# Sensors.net
KiCad netlist of a schematic drawn in Altium Designer
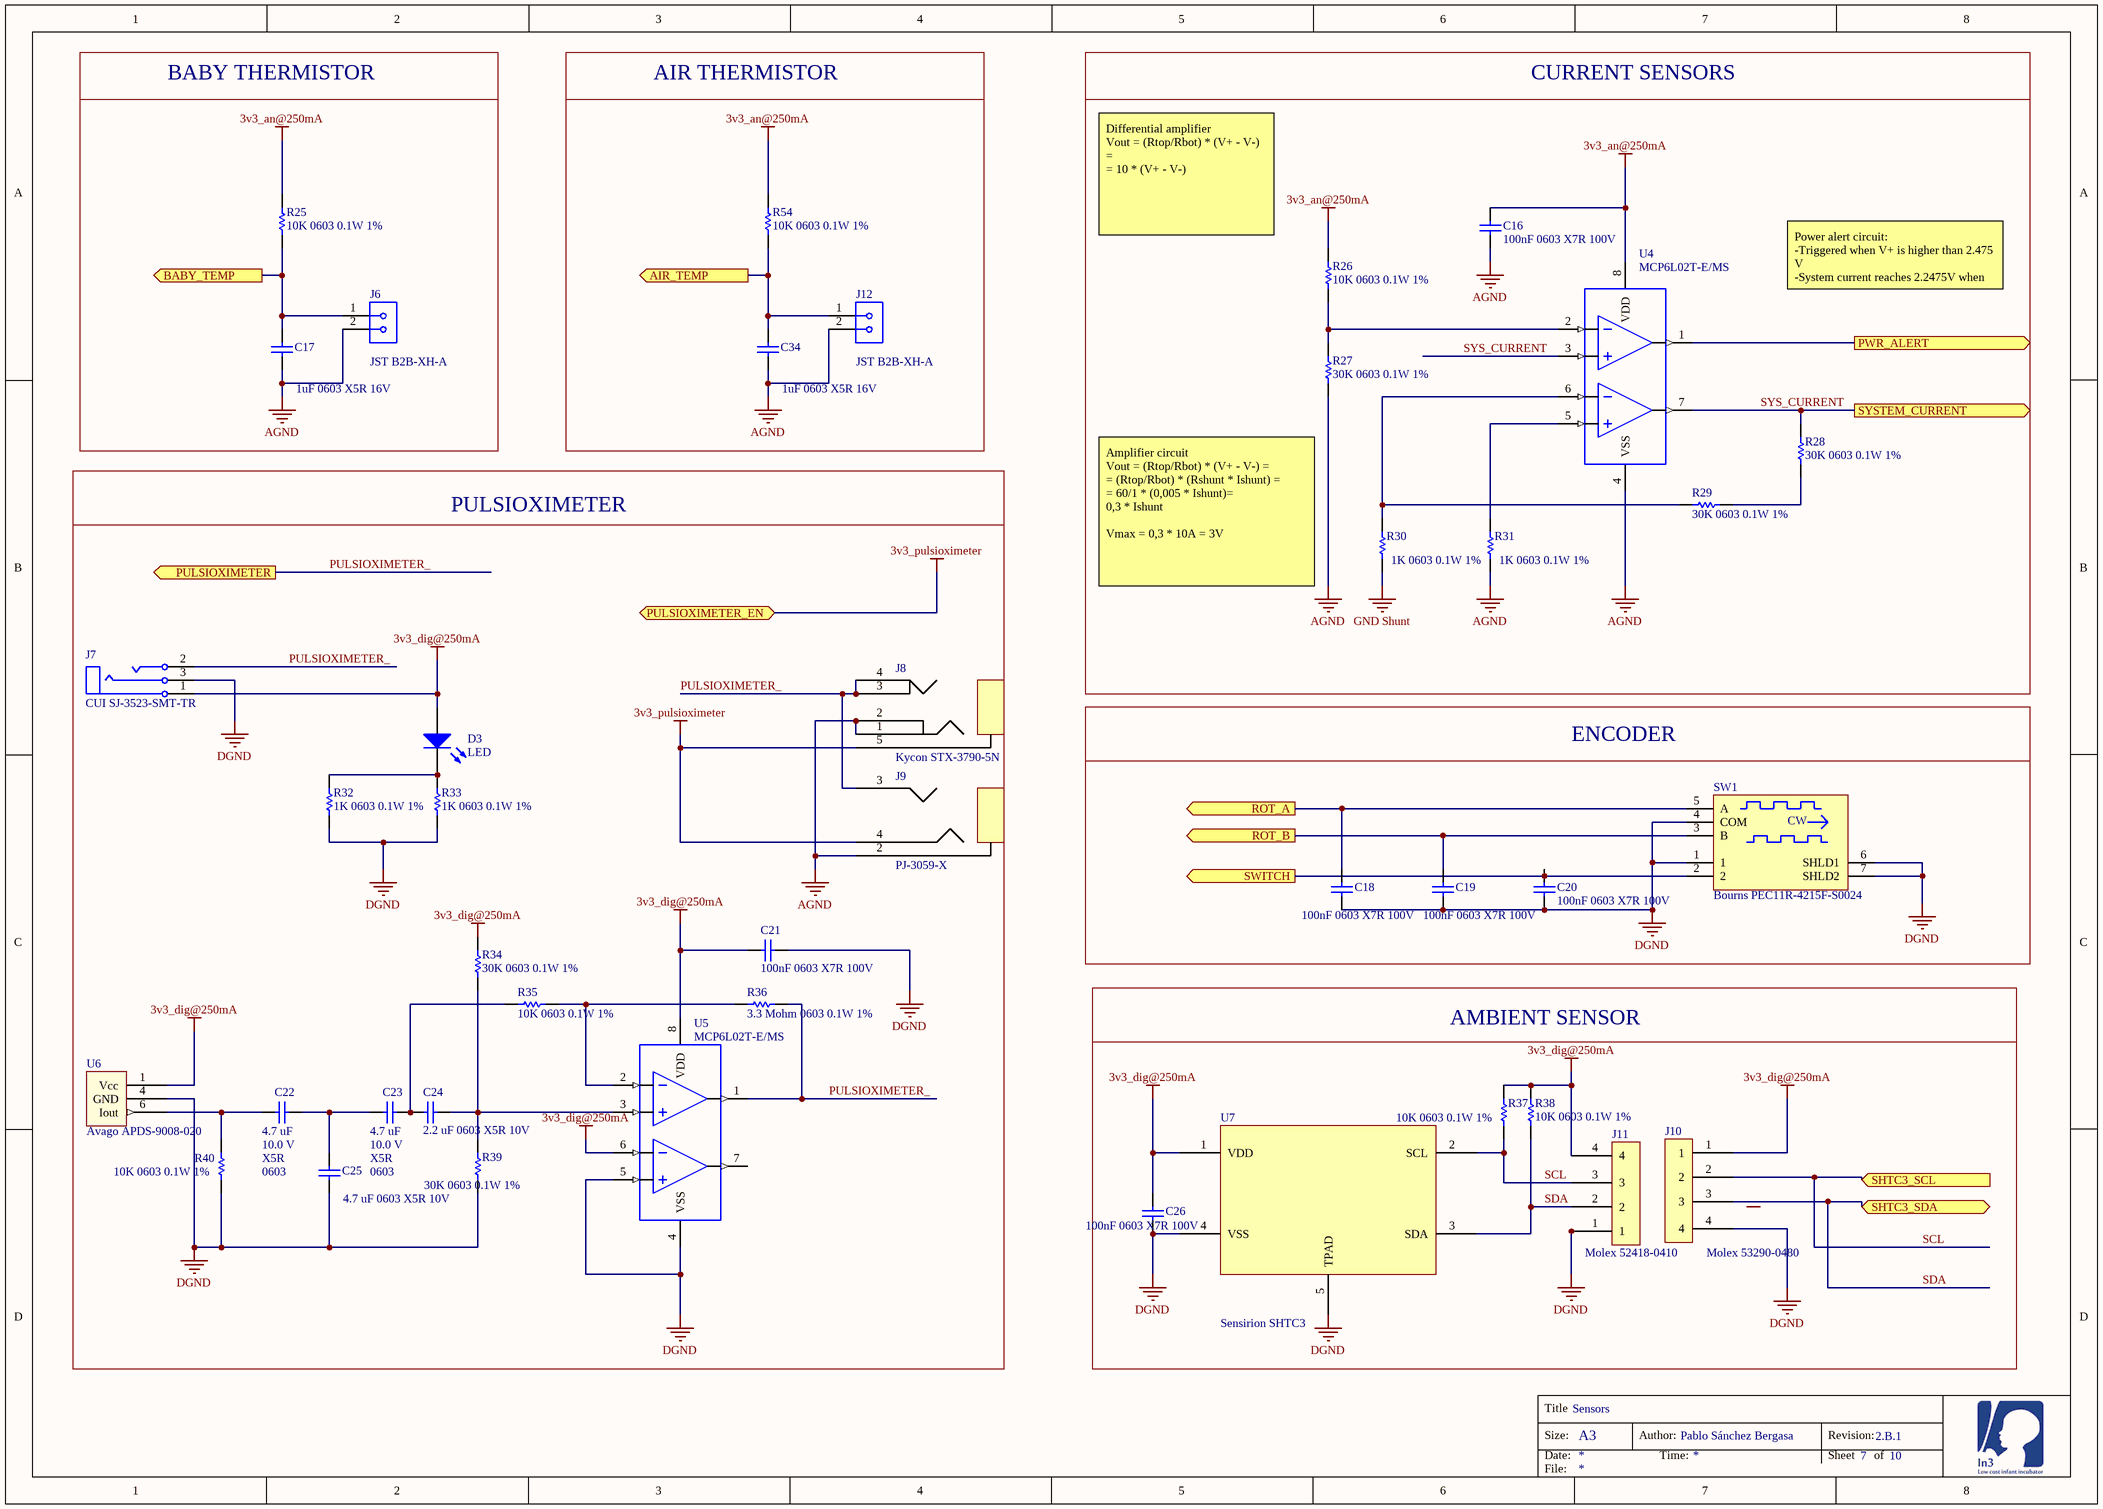
[diagram p0: Sensors.SchDoc]

(export (version "E")
  (design (tool "Eeschema 10.0.6"))
  (components
    (comp (ref "C16")
      (value "100nF 0603 X7R 100V")
      (footprint "CAPC1608X60X35NL10T15")
      (fields (field (name "MANUFACTURAR PART NUMBER") "CC0603KRX7R0BB104"))
      (libsource (lib "CommunityVault") (part "CMP-c41a0d2b65641bdd-3"))
    )
    (comp (ref "C17")
      (value "1uF 0603 X5R 16V")
      (footprint "CAPC1608X60X35NL10T15")
      (fields (field (name "MANUFACTURER PART NUMBER") "GRM185R61C105KE44D"))
      (libsource (lib "CommunityVault") (part "CMP-119984-2"))
    )
    (comp (ref "C18")
      (value "100nF 0603 X7R 100V")
      (footprint "CAPC1608X60X35NL10T15")
      (fields (field (name "MANUFACTURAR PART NUMBER") "CC0603KRX7R0BB104"))
      (libsource (lib "CommunityVault") (part "CMP-c41a0d2b65641bdd-3"))
    )
    (comp (ref "C19")
      (value "100nF 0603 X7R 100V")
      (footprint "CAPC1608X60X35NL10T15")
      (fields (field (name "MANUFACTURAR PART NUMBER") "CC0603KRX7R0BB104"))
      (libsource (lib "CommunityVault") (part "CMP-c41a0d2b65641bdd-3"))
    )
    (comp (ref "C20")
      (value "100nF 0603 X7R 100V")
      (footprint "CAPC1608X60X35NL10T15")
      (fields (field (name "MANUFACTURAR PART NUMBER") "CC0603KRX7R0BB104"))
      (libsource (lib "CommunityVault") (part "CMP-c41a0d2b65641bdd-3"))
    )
    (comp (ref "C21")
      (value "100nF 0603 X7R 100V")
      (footprint "CAPC1608X60X35NL10T15")
      (fields (field (name "MANUFACTURAR PART NUMBER") "CC0603KRX7R0BB104"))
      (libsource (lib "CommunityVault") (part "CMP-c41a0d2b65641bdd-3"))
    )
    (comp (ref "C22")
      (value "4.7 uF 0603 X5R 10V")
      (footprint "PCB-o44e25ijbg7jfnbnmamr-1")
      (description "CL10 Series 4.7 uF 10 V ±10 % Tolerance X5R SMT Multilayer Ceramic Capacitor")
      (fields
        (field (name "CAPACITANCE") "4.7 uF")
        (field (name "MANUFACTURER PART NUMBER") "CL10A475KP8NNNC")
        (field (name "DIELECTRIC CHARACTERISTIC") "X5R")
        (field (name "VOLTAGE RATING (DC)") "10.0 V")
        (field (name "CASE/PACKAGE") "0603")
      )
      (libsource (lib "CommunityVault") (part "CMP-4caf8516eb679368-2"))
    )
    (comp (ref "C23")
      (value "4.7 uF 0603 X5R 10V")
      (footprint "PCB-o44e25ijbg7jfnbnmamr-1")
      (description "CL10 Series 4.7 uF 10 V ±10 % Tolerance X5R SMT Multilayer Ceramic Capacitor")
      (fields
        (field (name "CAPACITANCE") "4.7 uF")
        (field (name "MANUFACTURER PART NUMBER") "CL10A475KP8NNNC")
        (field (name "DIELECTRIC CHARACTERISTIC") "X5R")
        (field (name "VOLTAGE RATING (DC)") "10.0 V")
        (field (name "CASE/PACKAGE") "0603")
      )
      (libsource (lib "CommunityVault") (part "CMP-4caf8516eb679368-2"))
    )
    (comp (ref "C24")
      (value "2.2 uF 0603 X5R 10V")
      (footprint "PCB-ut6qvzar43b06cy077h6-1")
      (description "Capacitor: ceramic; MLCC; 2.2uF; 10V; X5R; ±10%; SMD; 0603; -55÷85°C")
      (fields (field (name "MANUFACTURER PART NUMBER") "CL10A225KP8NNNC"))
      (libsource (lib "CommunityVault") (part "CMP-3568fc1ddfcfeaaf-3"))
    )
    (comp (ref "C25")
      (value "4.7 uF 0603 X5R 10V")
      (footprint "PCB-o44e25ijbg7jfnbnmamr-1")
      (description "CL10 Series 4.7 uF 10 V ±10 % Tolerance X5R SMT Multilayer Ceramic Capacitor")
      (fields (field (name "MANUFACTURER PART NUMBER") "CL10A475KP8NNNC"))
      (libsource (lib "CommunityVault") (part "CMP-4caf8516eb679368-2"))
    )
    (comp (ref "C26")
      (value "100nF 0603 X7R 100V")
      (footprint "CAPC1608X60X35NL10T15")
      (fields (field (name "MANUFACTURAR PART NUMBER") "CC0603KRX7R0BB104"))
      (libsource (lib "CommunityVault") (part "CMP-c41a0d2b65641bdd-3"))
    )
    (comp (ref "C34")
      (value "1uF 0603 X5R 16V")
      (footprint "CAPC1608X60X35NL10T15")
      (fields (field (name "MANUFACTURER PART NUMBER") "GRM185R61C105KE44D"))
      (libsource (lib "CommunityVault") (part "CMP-119984-2"))
    )
    (comp (ref "D3")
      (value "LED")
      (footprint "Diode")
      (description "Green 2.5 x 2 x 2.8 mm 20° Clear 2700 mcd 3.3 V Subminiature Solid State LED SMT")
      (fields (field (name "MANUFACTURER PART NUMBER") "AM2520ZGC09"))
      (libsource (lib "CommunityVault") (part "CMP-528b9bd0c0208d4c-1"))
    )
    (comp (ref "J6")
      (value "JST B2B-XH-A")
      (footprint "PCB-pp1at3pfx7vls1ur72ey-1")
      (description "Conn Shrouded Header HDR 2 POS 2.5mm Solder ST Thru-Hole Box")
      (fields (field (name "MANUFACTURER PART NUMBER") "B2B-XH-A"))
      (libsource (lib "CommunityVault") (part "CMP-1d67d451da9ec2a0-3"))
    )
    (comp (ref "J7")
      (value "CUI SJ-3523-SMT-TR")
      (footprint "PCB-wpf2idtw6ymbd7wafvje-1")
      (description "Conn 3.5MM Stereo Jack F 3 POS Solder RA SMD 3 Terminal 1 Port T/R")
      (fields (field (name "MANUFACTURER PART NUMBER") "SJ-3523-SMT-TR"))
      (libsource (lib "FavoritesLibrary") (part "SYM-9d6655e7545842a1-4"))
    )
    (comp (ref "J8")
      (value "Kycon STX-3790-5N")
      (footprint "PCB-4j7k1xhz8vc7zbr3u2za-1")
      (description "Conn Audio RCP 5 POS Solder ST Thru-Hole 5 Terminal 1 Port")
      (fields (field (name "MANUFACTURER PART NUMBER") "STX-3790-5N"))
      (libsource (lib "FavoritesLibrary") (part "SYM-d3711b49a5340cb6-1"))
    )
    (comp (ref "J9")
      (value "PJ-3059-X")
      (footprint "PCB-ylnrsqqp1zh2nrt13053-1")
      (description "3.5mm Plug-in headphone holder")
      (libsource (lib "CommunityVault") (part "CMP-qu24ppwf8ue4q4dth5co-2"))
    )
    (comp (ref "J10")
      (value "Molex 53290-0480")
      (footprint "PCB-az7j7v00du7ll54n3o04-1")
      (description "Molex; SER Number 53290; 2mm Pitch 4Way 1Row Straight PCB Header; Solder Term; 1.5A")
      (fields (field (name "MANUFACTURER PART NUMBER") "53290-0480"))
      (libsource (lib "FavoritesLibrary") (part "SYM-77b5bebc9fe3a872-1"))
    )
    (comp (ref "J11")
      (value "Molex 52418-0410")
      (footprint "PCB-2exqb8kt510pgx9iz0yo-1")
      (description "2.00mm Pitch Board-to-Board Receptacle, Right Angle, Single Row, Friction Lock, 4 Circuits")
      (fields (field (name "MANUFACTURER PART NUMBER") "52418-0410"))
      (libsource (lib "FavoritesLibrary") (part "SYM-efff26f6ba583038-1"))
    )
    (comp (ref "J12")
      (value "JST B2B-XH-A")
      (footprint "PCB-pp1at3pfx7vls1ur72ey-1")
      (description "Conn Shrouded Header HDR 2 POS 2.5mm Solder ST Thru-Hole Box")
      (fields (field (name "MANUFACTURER PART NUMBER") "B2B-XH-A"))
      (libsource (lib "CommunityVault") (part "CMP-1d67d451da9ec2a0-3"))
    )
    (comp (ref "R25")
      (value "10K 0603 0.1W 1%")
      (footprint "RESC1609X55X30ML10T20")
      (fields (field (name "TOLERANCE") "1%") (field (name "MANUFACTURER PART NUMBER") "ERJ-3GEYJ101V"))
      (libsource (lib "CommunityVault") (part "CMP-4716590-9"))
    )
    (comp (ref "R26")
      (value "10K 0603 0.1W 1%")
      (footprint "RESC1609X55X30ML10T20")
      (fields (field (name "TOLERANCE") "1%") (field (name "MANUFACTURER PART NUMBER") "ERJ-3GEYJ101V"))
      (libsource (lib "CommunityVault") (part "CMP-4716590-9"))
    )
    (comp (ref "R27")
      (value "30K 0603 0.1W 1%")
      (footprint "RESC1609X55X30ML10T20")
      (fields (field (name "TOLERANCE") "1%"))
      (libsource (lib "CommunityVault") (part "CMP-3655986-6"))
    )
    (comp (ref "R28")
      (value "30K 0603 0.1W 1%")
      (footprint "RESC1609X55X30ML10T20")
      (fields (field (name "TOLERANCE") "1%"))
      (libsource (lib "CommunityVault") (part "CMP-3655986-6"))
    )
    (comp (ref "R29")
      (value "30K 0603 0.1W 1%")
      (footprint "RESC1609X55X30ML10T20")
      (fields (field (name "TOLERANCE") "1%"))
      (libsource (lib "CommunityVault") (part "CMP-3655986-6"))
    )
    (comp (ref "R30")
      (value "1K 0603 0.1W 1%")
      (footprint "RESC1609X55X30ML10T20")
      (fields (field (name "MANUFACTURER PART NUMBER") "CR0603-FX-1001ELF"))
      (libsource (lib "CommunityVault") (part "CMP-a61f6f36030f79d8-4"))
    )
    (comp (ref "R31")
      (value "1K 0603 0.1W 1%")
      (footprint "RESC1609X55X30ML10T20")
      (fields (field (name "MANUFACTURER PART NUMBER") "CR0603-FX-1001ELF"))
      (libsource (lib "CommunityVault") (part "CMP-a61f6f36030f79d8-4"))
    )
    (comp (ref "R32")
      (value "1K 0603 0.1W 1%")
      (footprint "RESC1609X55X30ML10T20")
      (fields (field (name "MANUFACTURER PART NUMBER") "CR0603-FX-1001ELF"))
      (libsource (lib "CommunityVault") (part "CMP-a61f6f36030f79d8-4"))
    )
    (comp (ref "R33")
      (value "1K 0603 0.1W 1%")
      (footprint "RESC1609X55X30ML10T20")
      (fields (field (name "MANUFACTURER PART NUMBER") "CR0603-FX-1001ELF"))
      (libsource (lib "CommunityVault") (part "CMP-a61f6f36030f79d8-4"))
    )
    (comp (ref "R34")
      (value "30K 0603 0.1W 1%")
      (footprint "RESC1609X55X30ML10T20")
      (fields (field (name "TOLERANCE") "1%"))
      (libsource (lib "CommunityVault") (part "CMP-3655986-6"))
    )
    (comp (ref "R35")
      (value "10K 0603 0.1W 1%")
      (footprint "RESC1609X55X30ML10T20")
      (fields (field (name "TOLERANCE") "1%") (field (name "MANUFACTURER PART NUMBER") "ERJ-3GEYJ101V"))
      (libsource (lib "CommunityVault") (part "CMP-4716590-9"))
    )
    (comp (ref "R36")
      (value "3.3 Mohm 0603 0.1W 1%")
      (footprint "PCB-mzxdg9kz9211q53vmmjz-1")
      (description "Res Thick Film 1.6 x 0.8 mm 330K Ohm 1% 0.1W(1/10W) 100ppm/ C Molded SMD Paper T/R")
      (fields (field (name "MANUFACTURER PART NUMBER") "RC0603FR-07330KL"))
      (libsource (lib "CommunityVault") (part "CMP-0de3c699ccb2d224-2"))
    )
    (comp (ref "R37")
      (value "10K 0603 0.1W 1%")
      (footprint "RESC1609X55X30ML10T20")
      (fields (field (name "TOLERANCE") "1%") (field (name "MANUFACTURER PART NUMBER") "ERJ-3GEYJ101V"))
      (libsource (lib "CommunityVault") (part "CMP-4716590-9"))
    )
    (comp (ref "R38")
      (value "10K 0603 0.1W 1%")
      (footprint "RESC1609X55X30ML10T20")
      (fields (field (name "TOLERANCE") "1%") (field (name "MANUFACTURER PART NUMBER") "ERJ-3GEYJ101V"))
      (libsource (lib "CommunityVault") (part "CMP-4716590-9"))
    )
    (comp (ref "R39")
      (value "30K 0603 0.1W 1%")
      (footprint "RESC1609X55X30ML10T20")
      (fields (field (name "TOLERANCE") "1%"))
      (libsource (lib "CommunityVault") (part "CMP-3655986-6"))
    )
    (comp (ref "R40")
      (value "10K 0603 0.1W 1%")
      (footprint "RESC1609X55X30ML10T20")
      (fields (field (name "TOLERANCE") "1%") (field (name "MANUFACTURER PART NUMBER") "ERJ-3GEYJ101V"))
      (libsource (lib "CommunityVault") (part "CMP-4716590-9"))
    )
    (comp (ref "R54")
      (value "10K 0603 0.1W 1%")
      (footprint "RESC1609X55X30ML10T20")
      (fields (field (name "TOLERANCE") "1%") (field (name "MANUFACTURER PART NUMBER") "ERJ-3GEYJ101V"))
      (libsource (lib "CommunityVault") (part "CMP-4716590-9"))
    )
    (comp (ref "SW1")
      (value "Bourns PEC11R-4215F-S0024")
      (footprint "BOUR-PEC11R-4XXXF-SXXXX_V")
      (description "12 mm Incremental Encoder, 24 Detent, -30 to 70 degC, 5-Pin THD, RoHS, Bulk")
      (fields (field (name "MANUFACTURER PART NUMBER") "PEC11R-4215F-S0024"))
      (libsource (lib "FavoritesLibrary") (part "SW-ENCODER-5"))
    )
    (comp (ref "U4")
      (value "MCP6L02T-E/MS")
      (footprint "PCB-e8n0jpjj0ctkgxf737qv-1")
      (description "Microchip MCP6L02T-E/MS, Dual Op Amp, 1MHz Rail-Rail, 1.8 to 6 V, 8-Pin MSOP")
      (libsource (lib "CommunityVault") (part "CMP-1319549-4"))
    )
    (comp (ref "U5")
      (value "MCP6L02T-E/MS")
      (footprint "PCB-e8n0jpjj0ctkgxf737qv-1")
      (description "Microchip MCP6L02T-E/MS, Dual Op Amp, 1MHz Rail-Rail, 1.8 to 6 V, 8-Pin MSOP")
      (libsource (lib "CommunityVault") (part "CMP-1319549-4"))
    )
    (comp (ref "U6")
      (value "Avago APDS-9008-020")
      (footprint "PCB-5zuy5omviewwv0vuvsb9-1")
      (description "Ambient Light Sensor Photodetector 6-Pin SMD T/R")
      (fields (field (name "MANUFACTURER PART NUMBER") "APDS-9008-020"))
      (libsource (lib "CommunityVault") (part "SYM-1600df74f371c9c7-1"))
    )
    (comp (ref "U7")
      (value "Sensirion SHTC3")
      (footprint "DFN4 2x2 + EP")
      (description "Humidity & Temperature Sensor ±2% RH ±0, 2°C I2C DFN4")
      (libsource (lib "CommunityVault") (part "SHTC3"))
    )
  )
  (nets
    (net (code "1") (name "/AIR_TEMP") (class "Default")
      (node (ref "C34") (pin "1") (pinfunction "1_1") (pintype "passive"))
      (node (ref "J12") (pin "1") (pinfunction "1_1") (pintype "passive"))
      (node (ref "R54") (pin "2") (pinfunction "2_2") (pintype "passive"))
    )
    (net (code "2") (name "/BABY_TEMP") (class "Default")
      (node (ref "C17") (pin "1") (pinfunction "1_1") (pintype "passive"))
      (node (ref "J6") (pin "1") (pinfunction "1_1") (pintype "passive"))
      (node (ref "R25") (pin "2") (pinfunction "2_2") (pintype "passive"))
    )
    (net (code "3") (name "/PULSIOXIMETER_") (class "Default")
      (node (ref "J7") (pin "2") (pinfunction "TIP_2") (pintype "passive"))
      (node (ref "J8") (pin "3") (pinfunction "RIGHT_3") (pintype "passive"))
      (node (ref "J8") (pin "4") (pinfunction "LEFT_4") (pintype "passive"))
      (node (ref "J9") (pin "3") (pinfunction "LEFT_3") (pintype "passive"))
      (node (ref "R36") (pin "2") (pinfunction "2_2") (pintype "passive"))
      (node (ref "U5") (pin "1") (pinfunction "VOUTA_1") (pintype "output"))
    )
    (net (code "4") (name "/PWR_ALERT") (class "Default")
      (node (ref "U4") (pin "1") (pinfunction "VOUTA_1") (pintype "output"))
    )
    (net (code "5") (name "/ROT_A") (class "Default")
      (node (ref "C18") (pin "2") (pinfunction "2_2") (pintype "passive"))
      (node (ref "SW1") (pin "5") (pinfunction "A_5") (pintype "passive"))
    )
    (net (code "6") (name "/ROT_B") (class "Default")
      (node (ref "C19") (pin "2") (pinfunction "2_2") (pintype "passive"))
      (node (ref "SW1") (pin "3") (pinfunction "B_3") (pintype "passive"))
    )
    (net (code "7") (name "/SCL") (class "Default")
      (node (ref "J10") (pin "2") (pinfunction "2_2") (pintype "passive"))
      (node (ref "J11") (pin "3") (pinfunction "3_3") (pintype "passive"))
      (node (ref "R37") (pin "2") (pinfunction "2_2") (pintype "passive"))
      (node (ref "U7") (pin "2") (pinfunction "SCL_2") (pintype "passive"))
    )
    (net (code "8") (name "/SDA") (class "Default")
      (node (ref "J10") (pin "3") (pinfunction "3_3") (pintype "passive"))
      (node (ref "J11") (pin "2") (pinfunction "2_2") (pintype "passive"))
      (node (ref "R38") (pin "2") (pinfunction "2_2") (pintype "passive"))
      (node (ref "U7") (pin "3") (pinfunction "SDA_3") (pintype "passive"))
    )
    (net (code "9") (name "/SWITCH") (class "Default")
      (node (ref "C20") (pin "2") (pinfunction "2_2") (pintype "passive"))
      (node (ref "SW1") (pin "2") (pinfunction "2_2") (pintype "passive"))
    )
    (net (code "10") (name "/SYS_CURRENT") (class "Default")
      (node (ref "R28") (pin "1") (pinfunction "1_1") (pintype "passive"))
      (node (ref "U4") (pin "3") (pinfunction "VINA+_3") (pintype "input"))
      (node (ref "U4") (pin "7") (pinfunction "OUT_B_7") (pintype "output"))
    )
    (net (code "11") (name "3v3_an@250mA") (class "Default")
      (node (ref "C16") (pin "2") (pinfunction "2_2") (pintype "passive"))
      (node (ref "R25") (pin "1") (pinfunction "1_1") (pintype "passive"))
      (node (ref "R26") (pin "1") (pinfunction "1_1") (pintype "passive"))
      (node (ref "R54") (pin "1") (pinfunction "1_1") (pintype "passive"))
      (node (ref "U4") (pin "8") (pinfunction "VDD_8") (pintype "power_in"))
    )
    (net (code "12") (name "3v3_dig@250mA") (class "Default")
      (node (ref "C21") (pin "2") (pinfunction "2_2") (pintype "passive"))
      (node (ref "C26") (pin "2") (pinfunction "2_2") (pintype "passive"))
      (node (ref "D3") (pin "1") (pinfunction "A_1") (pintype "passive"))
      (node (ref "J10") (pin "1") (pinfunction "1_1") (pintype "passive"))
      (node (ref "J11") (pin "4") (pinfunction "4_4") (pintype "passive"))
      (node (ref "J7") (pin "1") (pinfunction "SLEEVE_1") (pintype "passive"))
      (node (ref "R34") (pin "1") (pinfunction "1_1") (pintype "passive"))
      (node (ref "R37") (pin "1") (pinfunction "1_1") (pintype "passive"))
      (node (ref "R38") (pin "1") (pinfunction "1_1") (pintype "passive"))
      (node (ref "U5") (pin "6") (pinfunction "VINB-_6") (pintype "input"))
      (node (ref "U5") (pin "8") (pinfunction "VDD_8") (pintype "power_in"))
      (node (ref "U6") (pin "1") (pinfunction "Vcc_1") (pintype "power_in"))
      (node (ref "U7") (pin "1") (pinfunction "VDD_1") (pintype "passive"))
    )
    (net (code "13") (name "3v3_pulsioximeter") (class "Default")
      (node (ref "J8") (pin "5") (pinfunction "GND_5") (pintype "passive"))
      (node (ref "J9") (pin "4") (pinfunction "RIGHT_4") (pintype "passive"))
    )
    (net (code "14") (name "AGND") (class "Default")
      (node (ref "C16") (pin "1") (pinfunction "1_1") (pintype "passive"))
      (node (ref "C17") (pin "2") (pinfunction "2_2") (pintype "passive"))
      (node (ref "C34") (pin "2") (pinfunction "2_2") (pintype "passive"))
      (node (ref "J12") (pin "2") (pinfunction "2_2") (pintype "passive"))
      (node (ref "J6") (pin "2") (pinfunction "2_2") (pintype "passive"))
      (node (ref "J8") (pin "1") (pinfunction "RIGHT_1") (pintype "passive"))
      (node (ref "J8") (pin "2") (pinfunction "RIGHT_2") (pintype "passive"))
      (node (ref "J9") (pin "2") (pinfunction "GND_2") (pintype "passive"))
      (node (ref "R27") (pin "2") (pinfunction "2_2") (pintype "passive"))
      (node (ref "R31") (pin "1") (pinfunction "1_1") (pintype "passive"))
      (node (ref "U4") (pin "4") (pinfunction "VSS_4") (pintype "power_in"))
    )
    (net (code "15") (name "DGND") (class "Default")
      (node (ref "C18") (pin "1") (pinfunction "1_1") (pintype "passive"))
      (node (ref "C19") (pin "1") (pinfunction "1_1") (pintype "passive"))
      (node (ref "C20") (pin "1") (pinfunction "1_1") (pintype "passive"))
      (node (ref "C21") (pin "1") (pinfunction "1_1") (pintype "passive"))
      (node (ref "C25") (pin "2") (pinfunction "2_2") (pintype "passive"))
      (node (ref "C26") (pin "1") (pinfunction "1_1") (pintype "passive"))
      (node (ref "J10") (pin "4") (pinfunction "4_4") (pintype "passive"))
      (node (ref "J11") (pin "1") (pinfunction "1_1") (pintype "passive"))
      (node (ref "J7") (pin "3") (pinfunction "RING_3") (pintype "passive"))
      (node (ref "R32") (pin "1") (pinfunction "1_1") (pintype "passive"))
      (node (ref "R33") (pin "1") (pinfunction "1_1") (pintype "passive"))
      (node (ref "R39") (pin "2") (pinfunction "2_2") (pintype "passive"))
      (node (ref "R40") (pin "1") (pinfunction "1_1") (pintype "passive"))
      (node (ref "SW1") (pin "1") (pinfunction "1_1") (pintype "passive"))
      (node (ref "SW1") (pin "4") (pinfunction "COM_4") (pintype "passive"))
      (node (ref "SW1") (pin "6") (pinfunction "SHLD1_6") (pintype "passive"))
      (node (ref "SW1") (pin "7") (pinfunction "SHLD2_7") (pintype "passive"))
      (node (ref "U5") (pin "4") (pinfunction "VSS_4") (pintype "power_in"))
      (node (ref "U5") (pin "5") (pinfunction "VINB+_5") (pintype "input"))
      (node (ref "U6") (pin "4") (pinfunction "GND_4") (pintype "power_in"))
      (node (ref "U7") (pin "4") (pinfunction "VSS_4") (pintype "passive"))
      (node (ref "U7") (pin "5") (pinfunction "TPAD_5") (pintype "passive"))
    )
    (net (code "16") (name "GND Shunt") (class "Default")
      (node (ref "R30") (pin "1") (pinfunction "1_1") (pintype "passive"))
    )
    (net (code "17") (name "Net-(C22-Pad1)") (class "Default")
      (node (ref "C22") (pin "1") (pinfunction "1_1") (pintype "passive"))
      (node (ref "C23") (pin "2") (pinfunction "2_2") (pintype "passive"))
      (node (ref "C25") (pin "1") (pinfunction "1_1") (pintype "passive"))
    )
    (net (code "18") (name "Net-(C23-Pad1)") (class "Default")
      (node (ref "C23") (pin "1") (pinfunction "1_1") (pintype "passive"))
      (node (ref "C24") (pin "2") (pinfunction "2_2") (pintype "passive"))
      (node (ref "R35") (pin "1") (pinfunction "1_1") (pintype "passive"))
    )
    (net (code "19") (name "Net-(D3-K)") (class "Default")
      (node (ref "D3") (pin "2") (pinfunction "K_2") (pintype "passive"))
      (node (ref "R32") (pin "2") (pinfunction "2_2") (pintype "passive"))
      (node (ref "R33") (pin "2") (pinfunction "2_2") (pintype "passive"))
    )
    (net (code "20") (name "Net-(R28-Pad2)") (class "Default")
      (node (ref "R28") (pin "2") (pinfunction "2_2") (pintype "passive"))
      (node (ref "R29") (pin "2") (pinfunction "2_2") (pintype "passive"))
    )
    (net (code "21") (name "Net-(U4-VINA-)") (class "Default")
      (node (ref "R26") (pin "2") (pinfunction "2_2") (pintype "passive"))
      (node (ref "R27") (pin "1") (pinfunction "1_1") (pintype "passive"))
      (node (ref "U4") (pin "2") (pinfunction "VINA-_2") (pintype "input"))
    )
    (net (code "22") (name "Net-(U4-VINB+)") (class "Default")
      (node (ref "R31") (pin "2") (pinfunction "2_2") (pintype "passive"))
      (node (ref "U4") (pin "5") (pinfunction "VINB+_5") (pintype "input"))
    )
    (net (code "23") (name "Net-(U4-VINB-)") (class "Default")
      (node (ref "R29") (pin "1") (pinfunction "1_1") (pintype "passive"))
      (node (ref "R30") (pin "2") (pinfunction "2_2") (pintype "passive"))
      (node (ref "U4") (pin "6") (pinfunction "VINB-_6") (pintype "input"))
    )
    (net (code "24") (name "Net-(U5-VINA+)") (class "Default")
      (node (ref "C24") (pin "1") (pinfunction "1_1") (pintype "passive"))
      (node (ref "R34") (pin "2") (pinfunction "2_2") (pintype "passive"))
      (node (ref "R39") (pin "1") (pinfunction "1_1") (pintype "passive"))
      (node (ref "U5") (pin "3") (pinfunction "VINA+_3") (pintype "input"))
    )
    (net (code "25") (name "Net-(U5-VINA-)") (class "Default")
      (node (ref "R35") (pin "2") (pinfunction "2_2") (pintype "passive"))
      (node (ref "R36") (pin "1") (pinfunction "1_1") (pintype "passive"))
      (node (ref "U5") (pin "2") (pinfunction "VINA-_2") (pintype "input"))
    )
    (net (code "26") (name "Net-(U6-Iout)") (class "Default")
      (node (ref "C22") (pin "2") (pinfunction "2_2") (pintype "passive"))
      (node (ref "R40") (pin "2") (pinfunction "2_2") (pintype "passive"))
      (node (ref "U6") (pin "6") (pinfunction "Iout_6") (pintype "output"))
    )
    (net (code "27") (name "unconnected-(U5-OUT_B-Pad7)") (class "Default")
      (node (ref "U5") (pin "7") (pinfunction "OUT_B_7") (pintype "output"))
    )
  )
)
